# MOTOR_DRIVER.net
KiCad netlist of a schematic drawn in Altium Designer
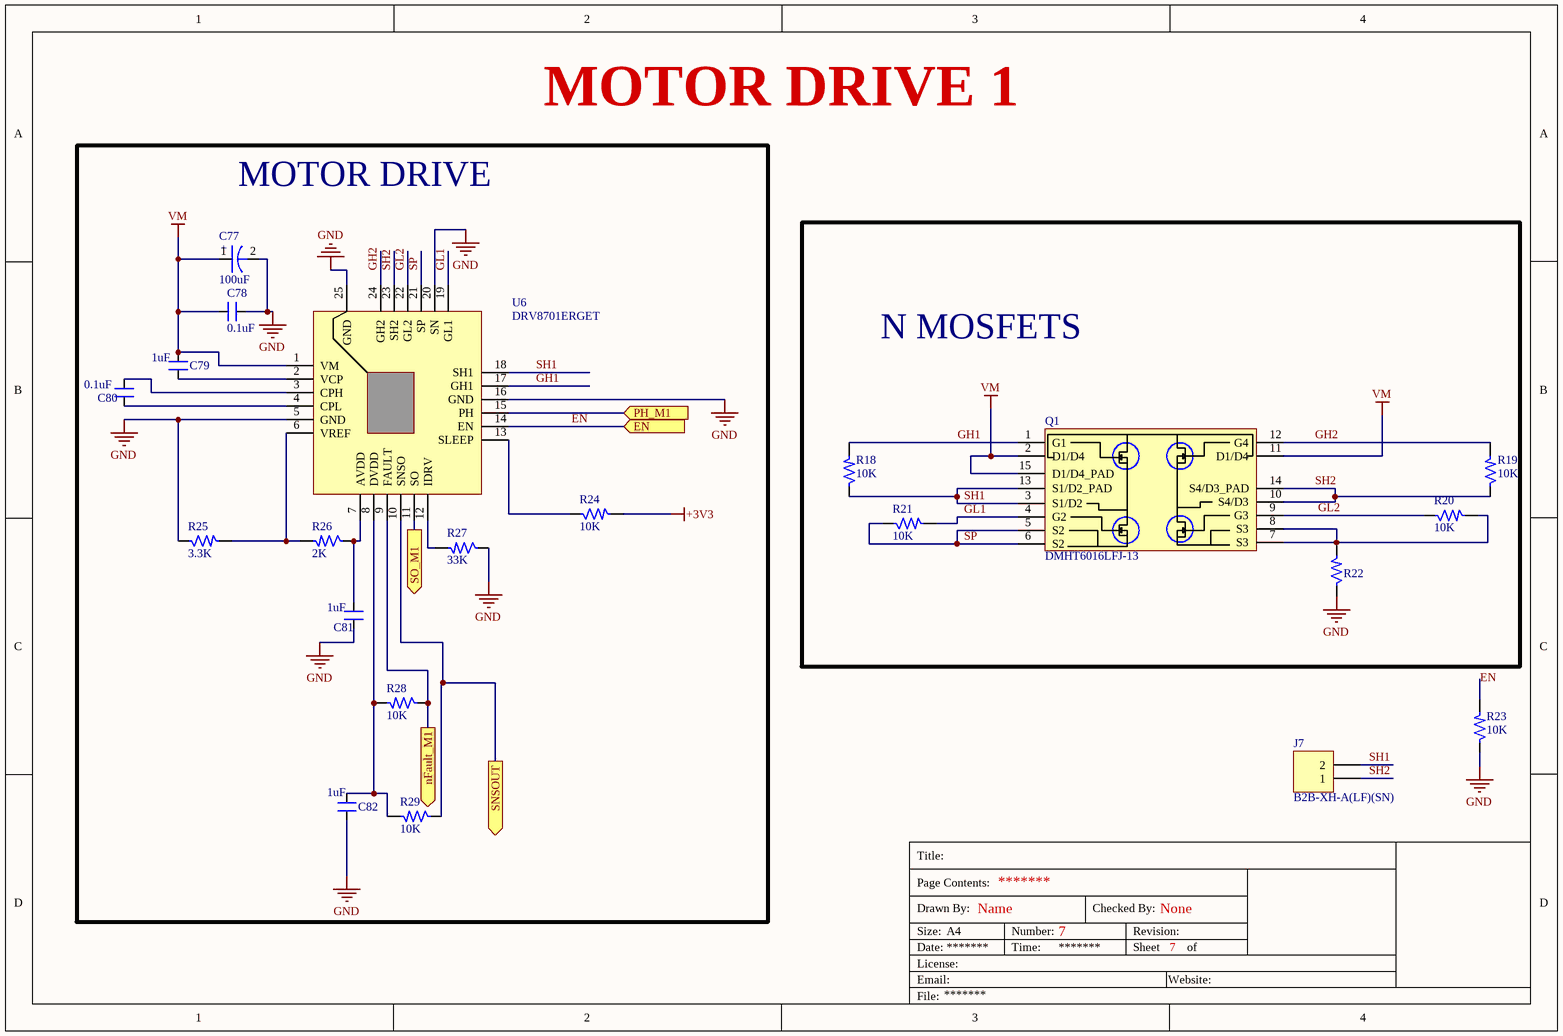
[diagram p0: MOTOR DRIVER.SchDoc]

(export (version "E")
  (design (tool "Eeschema 10.0.6"))
  (components
    (comp (ref "C77")
      (value "100uF")
      (footprint "ACAP_P236_D305_H303_RAD")
      (description "100µF 25V Aluminum Electrolytic Capacitors Radial, Can - SMD 1000 Hrs @ 105°C")
      (fields
        (field (name "MANUFACTURER") "Nichicon")
        (field (name "MANUFACTURER PART NUMBER") "UWT1E101MCL1GS")
      )
      (libsource (lib "ESTEEMPCBLIB") (part "CAP-P_100uF-25V-20%-RAD"))
    )
    (comp (ref "C78")
      (value "0.1uF")
      (footprint "CAP_0805")
      (description "0.1µF ±5% 50V Ceramic Capacitor X7R 0805 (2012 Metric)")
      (fields
        (field (name "MANUFACTURER") "AVX Corporation")
        (field (name "MANUFACTURER PART NUMBER") "08055C104JAT4A")
      )
      (libsource (lib "ESTEEMPCBLIB") (part "CAP_0.1uF-50V-5%-0805"))
    )
    (comp (ref "C79")
      (value "1uF")
      (footprint "CAP_0805")
      (description "1µF ±5% 50V Ceramic Capacitor X7R 0805 (2012 Metric)")
      (fields
        (field (name "MANUFACTURER") "Samsung")
        (field (name "MANUFACTURER PART NUMBER") "CC0805JKX7R9BB105")
      )
      (libsource (lib "ESTEEMPCBLIB") (part "CAP_1uF-50V-5%-0805"))
    )
    (comp (ref "C80")
      (value "0.1uF")
      (footprint "CAP_0805")
      (description "0.1µF ±5% 50V Ceramic Capacitor X7R 0805 (2012 Metric)")
      (fields
        (field (name "MANUFACTURER") "AVX Corporation")
        (field (name "MANUFACTURER PART NUMBER") "08055C104JAT4A")
      )
      (libsource (lib "ESTEEMPCBLIB") (part "CAP_0.1uF-50V-5%-0805"))
    )
    (comp (ref "C81")
      (value "1uF")
      (footprint "CAP_0805")
      (description "1µF ±5% 50V Ceramic Capacitor X7R 0805 (2012 Metric)")
      (fields
        (field (name "MANUFACTURER") "Samsung")
        (field (name "MANUFACTURER PART NUMBER") "CC0805JKX7R9BB105")
      )
      (libsource (lib "ESTEEMPCBLIB") (part "CAP_1uF-50V-5%-0805"))
    )
    (comp (ref "C82")
      (value "1uF")
      (footprint "CAP_0805")
      (description "1µF ±5% 50V Ceramic Capacitor X7R 0805 (2012 Metric)")
      (fields
        (field (name "MANUFACTURER") "Samsung")
        (field (name "MANUFACTURER PART NUMBER") "CC0805JKX7R9BB105")
      )
      (libsource (lib "ESTEEMPCBLIB") (part "CAP_1uF-50V-5%-0805"))
    )
    (comp (ref "J7")
      (value "B2B-XH-A(LF)(SN)")
      (footprint "CON2_100_B2B-XH-A_TH_ST")
      (description "2 Pins, 1 Row 2.54mm Pitch, Straight Connector, male")
      (fields (field (name "MANUFACTURER") "JST") (field (name "MATING PART NUMBER") "XHP-2"))
      (libsource (lib "ESTEEMPCBLIB") (part "CON-PLG_2X1-100-ST-TH"))
    )
    (comp (ref "Q1")
      (value "DMHT6016LFJ-13")
      (footprint "DFN5045-12_33_212_27X15_SMD_1")
      (description "Mosfet Array 4 N-Channel 14.8A (Ta) Surface Mount V-DFN5045-12")
      (fields (field (name "MANUFACTURER") "ON Semiconductor"))
      (libsource (lib "ESTEEMPCBLIB") (part "MOSFET-N_60V-14.8A-V-DFN5045-12"))
    )
    (comp (ref "R18")
      (value "10K")
      (footprint "RES_0805")
      (description "10 kOhms ±1% 0.125W, 1/8W Chip Resistor 0805 (2012 Metric) Automotive AEC-Q200 Thick Film")
      (fields (field (name "MANUFACTURER") "CTS") (field (name "MANUFACTURER PART NUMBER") "WR08X1002FTL"))
      (libsource (lib "ESTEEMPCBLIB") (part "RES_10K-0.125W-1%-0805"))
    )
    (comp (ref "R19")
      (value "10K")
      (footprint "RES_0805")
      (description "10 kOhms ±1% 0.125W, 1/8W Chip Resistor 0805 (2012 Metric) Automotive AEC-Q200 Thick Film")
      (fields (field (name "MANUFACTURER") "CTS") (field (name "MANUFACTURER PART NUMBER") "WR08X1002FTL"))
      (libsource (lib "ESTEEMPCBLIB") (part "RES_10K-0.125W-1%-0805"))
    )
    (comp (ref "R20")
      (value "10K")
      (footprint "RES_0805")
      (description "10 kOhms ±1% 0.125W, 1/8W Chip Resistor 0805 (2012 Metric) Automotive AEC-Q200 Thick Film")
      (fields (field (name "MANUFACTURER") "CTS") (field (name "MANUFACTURER PART NUMBER") "WR08X1002FTL"))
      (libsource (lib "ESTEEMPCBLIB") (part "RES_10K-0.125W-1%-0805"))
    )
    (comp (ref "R21")
      (value "10K")
      (footprint "RES_0805")
      (description "10 kOhms ±1% 0.125W, 1/8W Chip Resistor 0805 (2012 Metric) Automotive AEC-Q200 Thick Film")
      (fields (field (name "MANUFACTURER") "CTS") (field (name "MANUFACTURER PART NUMBER") "WR08X1002FTL"))
      (libsource (lib "ESTEEMPCBLIB") (part "RES_10K-0.125W-1%-0805"))
    )
    (comp (ref "R22")
      (value "RES_50mOHM-2W-2512 Current sense")
      (footprint "RESC6331X80N")
      (description "50 mOhms ±1% 2W Chip Resistor 2512 (6432 Metric) Current Sense Thick Film")
      (libsource (lib "ESTEEMPCBLIB") (part "RES_50mOHM-2W-2512 Current sense"))
    )
    (comp (ref "R23")
      (value "10K")
      (footprint "RES_0805")
      (description "10 kOhms ±1% 0.125W, 1/8W Chip Resistor 0805 (2012 Metric) Automotive AEC-Q200 Thick Film")
      (fields (field (name "MANUFACTURER") "CTS") (field (name "MANUFACTURER PART NUMBER") "WR08X1002FTL"))
      (libsource (lib "ESTEEMPCBLIB") (part "RES_10K-0.125W-1%-0805"))
    )
    (comp (ref "R24")
      (value "10K")
      (footprint "RES_0805")
      (description "10 kOhms ±1% 0.125W, 1/8W Chip Resistor 0805 (2012 Metric) Automotive AEC-Q200 Thick Film")
      (fields (field (name "MANUFACTURER") "CTS") (field (name "MANUFACTURER PART NUMBER") "WR08X1002FTL"))
      (libsource (lib "ESTEEMPCBLIB") (part "RES_10K-0.125W-1%-0805"))
    )
    (comp (ref "R25")
      (value "3.3K")
      (footprint "RES_0805")
      (description "3.3 kOhms ±1% 0.125W, 1/8W Chip Resistor 0805 (2012 Metric) Thick Film")
      (fields (field (name "MANUFACTURER") "Panasonic") (field (name "MANUFACTURER PART NUMBER") "1623214-1"))
      (libsource (lib "ESTEEMPCBLIB") (part "RES_3.3K-0.125W-1%-0805"))
    )
    (comp (ref "R26")
      (value "2K")
      (footprint "RES_0805")
      (description "2 kOhms ±1% 0.125W, 1/8W Chip Resistor 0805 (2012 Metric) Moisture Resistant Thick Film")
      (fields
        (field (name "MANUFACTURER") "TE Connectivity")
        (field (name "MANUFACTURER PART NUMBER") "RC0805FR-072KL")
      )
      (libsource (lib "ESTEEMPCBLIB") (part "RES_2K-0.125W-1%-0805"))
    )
    (comp (ref "R27")
      (value "33K")
      (footprint "RES_0805")
      (fields
        (field (name "MANUFACTURER") "Vishay BCcomponents")
        (field (name "MANUFACTURER PART NUMBER") "CRG0805F33K")
      )
      (libsource (lib "ESTEEMPCBLIB") (part "RES_33K-0.125W-1%-0805"))
    )
    (comp (ref "R28")
      (value "10K")
      (footprint "RES_0805")
      (description "10 kOhms ±1% 0.125W, 1/8W Chip Resistor 0805 (2012 Metric) Automotive AEC-Q200 Thick Film")
      (fields (field (name "MANUFACTURER") "CTS") (field (name "MANUFACTURER PART NUMBER") "WR08X1002FTL"))
      (libsource (lib "ESTEEMPCBLIB") (part "RES_10K-0.125W-1%-0805"))
    )
    (comp (ref "R29")
      (value "10K")
      (footprint "RES_0805")
      (description "10 kOhms ±1% 0.125W, 1/8W Chip Resistor 0805 (2012 Metric) Automotive AEC-Q200 Thick Film")
      (fields (field (name "MANUFACTURER") "CTS") (field (name "MANUFACTURER PART NUMBER") "WR08X1002FTL"))
      (libsource (lib "ESTEEMPCBLIB") (part "RES_10K-0.125W-1%-0805"))
    )
    (comp (ref "U6")
      (value "DRV8701ERGET")
      (footprint "VFQFN24_19.6_196_12X32_SMD_1")
      (description "Motor Driver Power MOSFET Parallel 24-VQFN (4x4)")
      (fields (field (name "MANUFACTURER") "Texas Instruments"))
      (libsource (lib "ESTEEMPCBLIB") (part "IC_DRV8701ERGET"))
    )
  )
  (nets
    (net (code "1") (name "+3V3") (class "Default")
      (node (ref "R24") (pin "2") (pinfunction "2_2") (pintype "passive"))
    )
    (net (code "2") (name "/EN") (class "Default")
      (node (ref "R23") (pin "2") (pinfunction "2_2") (pintype "passive"))
      (node (ref "U6") (pin "14") (pinfunction "EN_14") (pintype "passive"))
    )
    (net (code "3") (name "/GH1") (class "Default")
      (node (ref "Q1") (pin "1") (pinfunction "G1_1") (pintype "passive"))
      (node (ref "R18") (pin "2") (pinfunction "2_2") (pintype "passive"))
      (node (ref "U6") (pin "17") (pinfunction "GH1_17") (pintype "passive"))
    )
    (net (code "4") (name "/GH2") (class "Default")
      (node (ref "Q1") (pin "12") (pinfunction "G4_12") (pintype "passive"))
      (node (ref "R19") (pin "2") (pinfunction "2_2") (pintype "passive"))
      (node (ref "U6") (pin "24") (pinfunction "GH2_24") (pintype "passive"))
    )
    (net (code "5") (name "/GL1") (class "Default")
      (node (ref "Q1") (pin "4") (pinfunction "G2_4") (pintype "passive"))
      (node (ref "R21") (pin "2") (pinfunction "2_2") (pintype "passive"))
      (node (ref "U6") (pin "19") (pinfunction "GL1_19") (pintype "passive"))
    )
    (net (code "6") (name "/GL2") (class "Default")
      (node (ref "Q1") (pin "9") (pinfunction "G3_9") (pintype "passive"))
      (node (ref "R20") (pin "1") (pinfunction "1_1") (pintype "passive"))
      (node (ref "U6") (pin "22") (pinfunction "GL2_22") (pintype "passive"))
    )
    (net (code "7") (name "/PH_M1") (class "Default")
      (node (ref "U6") (pin "15") (pinfunction "PH_15") (pintype "passive"))
    )
    (net (code "8") (name "/SH1") (class "Default")
      (node (ref "J7") (pin "2") (pinfunction "2_2") (pintype "passive"))
      (node (ref "Q1") (pin "13") (pinfunction "S1/D2_PAD_13") (pintype "passive"))
      (node (ref "Q1") (pin "3") (pinfunction "S1/D2_3") (pintype "passive"))
      (node (ref "R18") (pin "1") (pinfunction "1_1") (pintype "passive"))
      (node (ref "U6") (pin "18") (pinfunction "SH1_18") (pintype "passive"))
    )
    (net (code "9") (name "/SH2") (class "Default")
      (node (ref "J7") (pin "1") (pinfunction "1_1") (pintype "passive"))
      (node (ref "Q1") (pin "10") (pinfunction "S4/D3_10") (pintype "passive"))
      (node (ref "Q1") (pin "14") (pinfunction "S4/D3_PAD_14") (pintype "passive"))
      (node (ref "R19") (pin "1") (pinfunction "1_1") (pintype "passive"))
      (node (ref "U6") (pin "23") (pinfunction "SH2_23") (pintype "passive"))
    )
    (net (code "10") (name "/SNSOUT") (class "Default")
      (node (ref "R29") (pin "1") (pinfunction "1_1") (pintype "passive"))
      (node (ref "U6") (pin "10") (pinfunction "SNSO_10") (pintype "passive"))
    )
    (net (code "11") (name "/SO_M1") (class "Default")
      (node (ref "U6") (pin "11") (pinfunction "SO_11") (pintype "passive"))
    )
    (net (code "12") (name "/SP") (class "Default")
      (node (ref "Q1") (pin "5") (pinfunction "S2_5") (pintype "passive"))
      (node (ref "Q1") (pin "6") (pinfunction "S2_6") (pintype "passive"))
      (node (ref "R21") (pin "1") (pinfunction "1_1") (pintype "passive"))
      (node (ref "U6") (pin "21") (pinfunction "SP_21") (pintype "passive"))
    )
    (net (code "13") (name "/nFault_M1") (class "Default")
      (node (ref "R28") (pin "1") (pinfunction "1_1") (pintype "passive"))
      (node (ref "U6") (pin "9") (pinfunction "FAULT_9") (pintype "passive"))
    )
    (net (code "14") (name "GND") (class "Default")
      (node (ref "C77") (pin "2") (pinfunction "2_2") (pintype "passive"))
      (node (ref "C78") (pin "2") (pinfunction "2_2") (pintype "passive"))
      (node (ref "C81") (pin "1") (pinfunction "1_1") (pintype "passive"))
      (node (ref "C82") (pin "1") (pinfunction "1_1") (pintype "passive"))
      (node (ref "R22") (pin "1") (pinfunction "1_1") (pintype "passive"))
      (node (ref "R23") (pin "1") (pinfunction "1_1") (pintype "passive"))
      (node (ref "R25") (pin "1") (pinfunction "1_1") (pintype "passive"))
      (node (ref "R27") (pin "1") (pinfunction "1_1") (pintype "passive"))
      (node (ref "U6") (pin "16") (pinfunction "GND_16") (pintype "passive"))
      (node (ref "U6") (pin "20") (pinfunction "SN_20") (pintype "passive"))
      (node (ref "U6") (pin "25") (pinfunction "GND_25") (pintype "passive"))
      (node (ref "U6") (pin "5") (pinfunction "GND_5") (pintype "passive"))
    )
    (net (code "15") (name "Net-(Q1-S3-Pad7)") (class "Default")
      (node (ref "Q1") (pin "7") (pinfunction "S3_7") (pintype "passive"))
      (node (ref "Q1") (pin "8") (pinfunction "S3_8") (pintype "passive"))
      (node (ref "R20") (pin "2") (pinfunction "2_2") (pintype "passive"))
      (node (ref "R22") (pin "2") (pinfunction "2_2") (pintype "passive"))
    )
    (net (code "16") (name "Net-(U6-AVDD)") (class "Default")
      (node (ref "C81") (pin "2") (pinfunction "2_2") (pintype "passive"))
      (node (ref "R26") (pin "1") (pinfunction "1_1") (pintype "passive"))
      (node (ref "U6") (pin "7") (pinfunction "AVDD_7") (pintype "passive"))
    )
    (net (code "17") (name "Net-(U6-CPH)") (class "Default")
      (node (ref "C80") (pin "2") (pinfunction "2_2") (pintype "passive"))
      (node (ref "U6") (pin "3") (pinfunction "CPH_3") (pintype "passive"))
    )
    (net (code "18") (name "Net-(U6-CPL)") (class "Default")
      (node (ref "C80") (pin "1") (pinfunction "1_1") (pintype "passive"))
      (node (ref "U6") (pin "4") (pinfunction "CPL_4") (pintype "passive"))
    )
    (net (code "19") (name "Net-(U6-DVDD)") (class "Default")
      (node (ref "C82") (pin "2") (pinfunction "2_2") (pintype "passive"))
      (node (ref "R28") (pin "2") (pinfunction "2_2") (pintype "passive"))
      (node (ref "R29") (pin "2") (pinfunction "2_2") (pintype "passive"))
      (node (ref "U6") (pin "8") (pinfunction "DVDD_8") (pintype "passive"))
    )
    (net (code "20") (name "Net-(U6-IDRV)") (class "Default")
      (node (ref "R27") (pin "2") (pinfunction "2_2") (pintype "passive"))
      (node (ref "U6") (pin "12") (pinfunction "IDRV_12") (pintype "passive"))
    )
    (net (code "21") (name "Net-(U6-SLEEP)") (class "Default")
      (node (ref "R24") (pin "1") (pinfunction "1_1") (pintype "passive"))
      (node (ref "U6") (pin "13") (pinfunction "SLEEP_13") (pintype "passive"))
    )
    (net (code "22") (name "Net-(U6-VCP)") (class "Default")
      (node (ref "C79") (pin "1") (pinfunction "1_1") (pintype "passive"))
      (node (ref "U6") (pin "2") (pinfunction "VCP_2") (pintype "passive"))
    )
    (net (code "23") (name "Net-(U6-VREF)") (class "Default")
      (node (ref "R25") (pin "2") (pinfunction "2_2") (pintype "passive"))
      (node (ref "R26") (pin "2") (pinfunction "2_2") (pintype "passive"))
      (node (ref "U6") (pin "6") (pinfunction "VREF_6") (pintype "passive"))
    )
    (net (code "24") (name "VM") (class "Default")
      (node (ref "C77") (pin "1") (pinfunction "1_1") (pintype "passive"))
      (node (ref "C78") (pin "1") (pinfunction "1_1") (pintype "passive"))
      (node (ref "C79") (pin "2") (pinfunction "2_2") (pintype "passive"))
      (node (ref "Q1") (pin "11") (pinfunction "D1/D4_11") (pintype "passive"))
      (node (ref "Q1") (pin "15") (pinfunction "D1/D4_PAD_15") (pintype "passive"))
      (node (ref "Q1") (pin "2") (pinfunction "D1/D4_2") (pintype "passive"))
      (node (ref "U6") (pin "1") (pinfunction "VM_1") (pintype "passive"))
    )
  )
)
